# ServoMotor.net
KiCad netlist of a schematic drawn in EAGLE
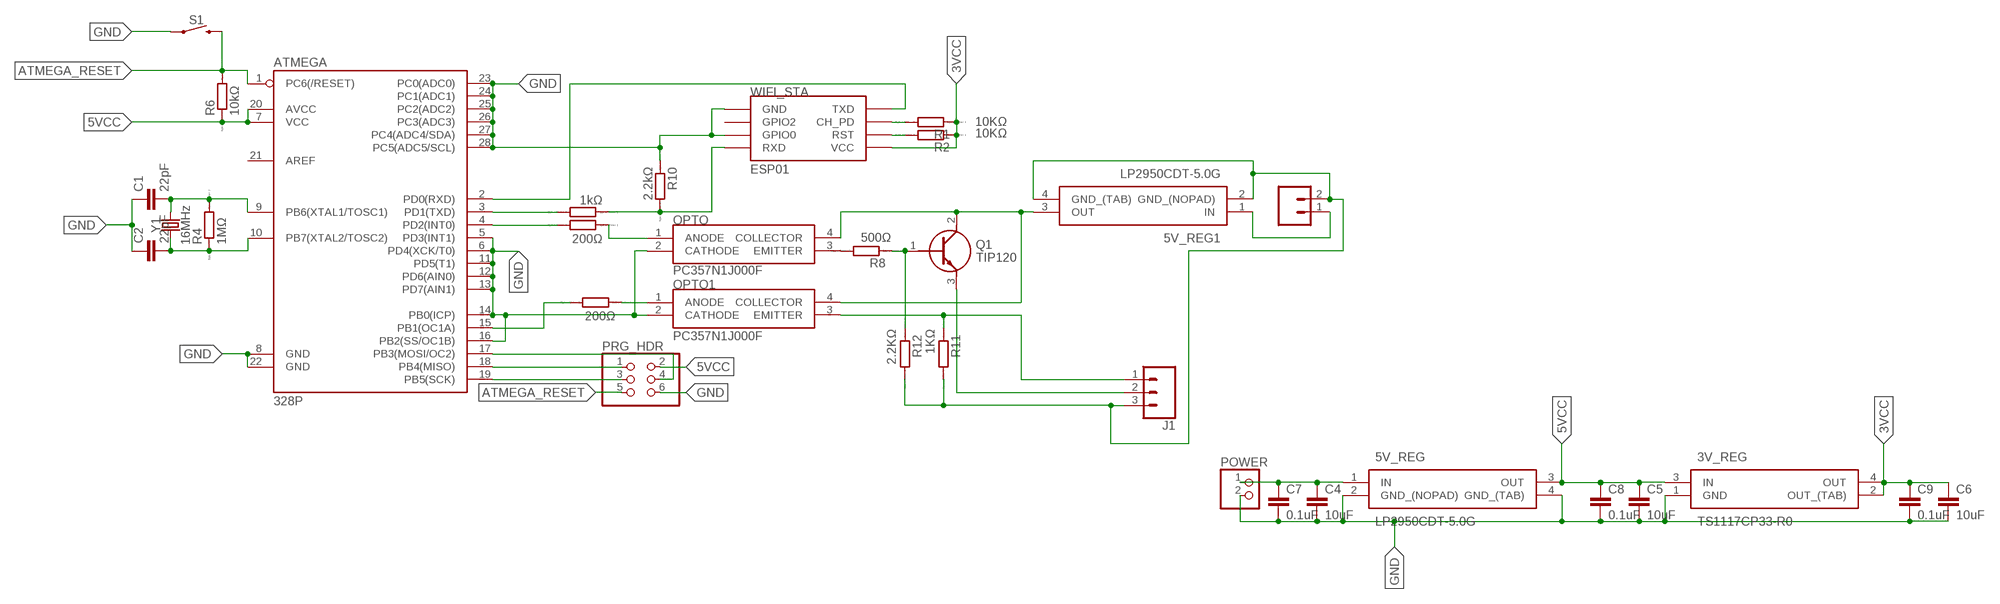
[diagram p0: schematic, sheet 1]

(export (version "E")
  (design (tool "Eeschema 10.0.6"))
  (components
    (comp (ref "3V_REG")
      (value "TS1117CP33-R0")
      (footprint "eagle-import:TO229P990X238-4N")
      (fields
        (field (name "MANUFACTURER_PART_NUMBER") "LP2950CDT-5.0G")
        (field (name "MOUSER_PART_NUMBER") "863-LP2950CDT-5.0G")
        (field (name "RS_PART_NUMBER") "0463593P")
      )
      (libsource (lib "eagle-import") (part "TS1117CP33-R0"))
    )
    (comp (ref "5V_REG")
      (value "LP2950CDT-5.0G")
      (footprint "eagle-import:TO229P990X238-4N")
      (fields
        (field (name "MOUSER_PART_NUMBER") "863-LP2950CDT-5.0G")
        (field (name "RS_PART_NUMBER") "0463593P")
      )
      (libsource (lib "eagle-import") (part "LP2950CDT-5.0G"))
    )
    (comp (ref "5V_REG1")
      (value "LP2950CDT-5.0G")
      (footprint "eagle-import:TO229P990X238-4N")
      (fields
        (field (name "MOUSER_PART_NUMBER") "863-LP2950CDT-5.0G")
        (field (name "RS_PART_NUMBER") "0463593P")
      )
      (libsource (lib "eagle-import") (part "LP2950CDT-5.0G"))
    )
    (comp (ref "ATMEGA")
      (value "328P")
      (footprint "eagle-import:DIP28")
      (libsource (lib "eagle-import") (part "ATMEGA328P_PDIP"))
    )
    (comp (ref "C1")
      (value "22pF")
      (footprint "eagle-import:1206")
      (libsource (lib "eagle-import") (part "1.0UF-1206-50V-10%"))
    )
    (comp (ref "C2")
      (value "22pF")
      (footprint "eagle-import:1206")
      (libsource (lib "eagle-import") (part "1.0UF-1206-50V-10%"))
    )
    (comp (ref "C4")
      (value "10uF")
      (footprint "eagle-import:1206")
      (libsource (lib "eagle-import") (part "1.0UF-1206-50V-10%"))
    )
    (comp (ref "C5")
      (value "10uF")
      (footprint "eagle-import:1206")
      (libsource (lib "eagle-import") (part "1.0UF-1206-50V-10%"))
    )
    (comp (ref "C6")
      (value "10uF")
      (footprint "eagle-import:1206")
      (libsource (lib "eagle-import") (part "1.0UF-1206-50V-10%"))
    )
    (comp (ref "C7")
      (value "0.1uF")
      (footprint "eagle-import:1206")
      (libsource (lib "eagle-import") (part "1.0UF-1206-50V-10%"))
    )
    (comp (ref "C8")
      (value "0.1uF")
      (footprint "eagle-import:1206")
      (libsource (lib "eagle-import") (part "1.0UF-1206-50V-10%"))
    )
    (comp (ref "C9")
      (value "0.1uF")
      (footprint "eagle-import:1206")
      (libsource (lib "eagle-import") (part "1.0UF-1206-50V-10%"))
    )
    (comp (ref "J1")
      (value "CONN_03")
      (footprint "eagle-import:1X03")
      (libsource (lib "eagle-import") (part "CONN_03"))
    )
    (comp (ref "OPTO")
      (value "PC357N1J000F")
      (footprint "eagle-import:SOP254P675X300-4N")
      (fields
        (field (name "MOUSER_PART_NUMBER") "852-PC357N1J000F")
        (field (name "RS_PART_NUMBER") "1460767")
      )
      (libsource (lib "eagle-import") (part "PC357N1J000F"))
    )
    (comp (ref "OPTO1")
      (value "PC357N1J000F")
      (footprint "eagle-import:SOP254P675X300-4N")
      (fields
        (field (name "MOUSER_PART_NUMBER") "852-PC357N1J000F")
        (field (name "RS_PART_NUMBER") "1460767")
      )
      (libsource (lib "eagle-import") (part "PC357N1J000F"))
    )
    (comp (ref "POWER")
      (value "PINHD-1X2")
      (footprint "eagle-import:1X02")
      (libsource (lib "eagle-import") (part "PINHD-1X2"))
    )
    (comp (ref "PRG_HDR")
      (value "PINHD-2X3")
      (footprint "eagle-import:2X03")
      (libsource (lib "eagle-import") (part "PINHD-2X3"))
    )
    (comp (ref "PWR_SERVO")
      (value "CONN_025MM")
      (footprint "eagle-import:SCREWTERMINAL-5MM-2")
      (libsource (lib "eagle-import") (part "CONN_025MM"))
    )
    (comp (ref "Q1")
      (value "TIP120")
      (footprint "eagle-import:TO220")
      (fields (field (name "MOUSER_PART_NUMBER") "512-TIP120"))
      (libsource (lib "eagle-import") (part "TIP120"))
    )
    (comp (ref "R1")
      (value "10KΩ")
      (footprint "eagle-import:R1210")
      (libsource (lib "eagle-import") (part "RR1210"))
    )
    (comp (ref "R2")
      (value "10KΩ")
      (footprint "eagle-import:R1210")
      (libsource (lib "eagle-import") (part "RR1210"))
    )
    (comp (ref "R3")
      (value "200Ω")
      (footprint "eagle-import:R1210")
      (libsource (lib "eagle-import") (part "RR1210"))
    )
    (comp (ref "R4")
      (value "1MΩ")
      (footprint "eagle-import:R1210")
      (libsource (lib "eagle-import") (part "RR1210"))
    )
    (comp (ref "R5")
      (value "200Ω")
      (footprint "eagle-import:R1210")
      (libsource (lib "eagle-import") (part "RR1210"))
    )
    (comp (ref "R6")
      (value "10kΩ")
      (footprint "eagle-import:R1210")
      (libsource (lib "eagle-import") (part "RR1210"))
    )
    (comp (ref "R8")
      (value "500Ω")
      (footprint "eagle-import:R1210")
      (libsource (lib "eagle-import") (part "RR1210"))
    )
    (comp (ref "R9")
      (value "1kΩ")
      (footprint "eagle-import:R1210")
      (libsource (lib "eagle-import") (part "RR1210"))
    )
    (comp (ref "R10")
      (value "2.2kΩ")
      (footprint "eagle-import:R1210")
      (libsource (lib "eagle-import") (part "RR1210"))
    )
    (comp (ref "R11")
      (value "1KΩ")
      (footprint "eagle-import:R1210")
      (libsource (lib "eagle-import") (part "RR1210"))
    )
    (comp (ref "R12")
      (value "2.2KΩ")
      (footprint "eagle-import:R1210")
      (libsource (lib "eagle-import") (part "RR1210"))
    )
    (comp (ref "S1")
      (value "MOMENTARY-SWITCH-SPST-PTH-6.0MM")
      (footprint "eagle-import:TACTILE_SWITCH_PTH_6.0MM")
      (libsource (lib "eagle-import") (part "MOMENTARY-SWITCH-SPST-PTH-6.0MM"))
    )
    (comp (ref "WIFI_STA")
      (value "ESP01")
      (footprint "eagle-import:ESP01")
      (libsource (lib "eagle-import") (part "ESP01"))
    )
    (comp (ref "Y1")
      (value "16MHz")
      (footprint "eagle-import:HC49UP")
      (libsource (lib "eagle-import") (part "CRYSTAL-8MHZSMD-HC49UP"))
    )
  )
  (nets
    (net (code "1") (name "3VCC") (class "Default")
      (node (ref "3V_REG") (pin "2") (pinfunction "OUT_(TAB)_2") (pintype "output"))
      (node (ref "3V_REG") (pin "4") (pinfunction "OUT_4") (pintype "output"))
      (node (ref "C6") (pin "1") (pinfunction "1_1") (pintype "passive"))
      (node (ref "C9") (pin "1") (pinfunction "1_1") (pintype "passive"))
      (node (ref "R1") (pin "1") (pinfunction "1_1") (pintype "passive"))
      (node (ref "R2") (pin "1") (pinfunction "1_1") (pintype "passive"))
      (node (ref "WIFI_STA") (pin "VCC") (pinfunction "VCC_VCC") (pintype "bidirectional"))
    )
    (net (code "2") (name "5VCC") (class "Default")
      (node (ref "3V_REG") (pin "3") (pinfunction "IN_3") (pintype "input"))
      (node (ref "5V_REG") (pin "3") (pinfunction "OUT_3") (pintype "output"))
      (node (ref "ATMEGA") (pin "20") (pinfunction "AVCC_20") (pintype "bidirectional"))
      (node (ref "ATMEGA") (pin "7") (pinfunction "VCC_7") (pintype "bidirectional"))
      (node (ref "C5") (pin "1") (pinfunction "1_1") (pintype "passive"))
      (node (ref "C8") (pin "1") (pinfunction "1_1") (pintype "passive"))
      (node (ref "PRG_HDR") (pin "2") (pinfunction "2_2") (pintype "passive"))
      (node (ref "R6") (pin "1") (pinfunction "1_1") (pintype "passive"))
    )
    (net (code "3") (name "ATMEGA_RESET") (class "Default")
      (node (ref "ATMEGA") (pin "1") (pinfunction "PC6(/RESET)_1") (pintype "bidirectional"))
      (node (ref "PRG_HDR") (pin "5") (pinfunction "5_5") (pintype "passive"))
      (node (ref "R6") (pin "2") (pinfunction "2_2") (pintype "passive"))
      (node (ref "S1") (pin "3") (pinfunction "2_3") (pintype "passive"))
    )
    (net (code "4") (name "GND") (class "Default")
      (node (ref "3V_REG") (pin "1") (pinfunction "GND_1") (pintype "power_in"))
      (node (ref "5V_REG") (pin "2") (pinfunction "GND_(NOPAD)_2") (pintype "power_in"))
      (node (ref "5V_REG") (pin "4") (pinfunction "GND_(TAB)_4") (pintype "power_in"))
      (node (ref "ATMEGA") (pin "11") (pinfunction "PD5(T1)_11") (pintype "bidirectional"))
      (node (ref "ATMEGA") (pin "12") (pinfunction "PD6(AIN0)_12") (pintype "bidirectional"))
      (node (ref "ATMEGA") (pin "13") (pinfunction "PD7(AIN1)_13") (pintype "bidirectional"))
      (node (ref "ATMEGA") (pin "14") (pinfunction "PB0(ICP)_14") (pintype "bidirectional"))
      (node (ref "ATMEGA") (pin "16") (pinfunction "PB2(SS/OC1B)_16") (pintype "bidirectional"))
      (node (ref "ATMEGA") (pin "22") (pinfunction "GND_22") (pintype "bidirectional"))
      (node (ref "ATMEGA") (pin "23") (pinfunction "PC0(ADC0)_23") (pintype "bidirectional"))
      (node (ref "ATMEGA") (pin "24") (pinfunction "PC1(ADC1)_24") (pintype "bidirectional"))
      (node (ref "ATMEGA") (pin "25") (pinfunction "PC2(ADC2)_25") (pintype "bidirectional"))
      (node (ref "ATMEGA") (pin "26") (pinfunction "PC3(ADC3)_26") (pintype "bidirectional"))
      (node (ref "ATMEGA") (pin "27") (pinfunction "PC4(ADC4/SDA)_27") (pintype "bidirectional"))
      (node (ref "ATMEGA") (pin "28") (pinfunction "PC5(ADC5/SCL)_28") (pintype "bidirectional"))
      (node (ref "ATMEGA") (pin "5") (pinfunction "PD3(INT1)_5") (pintype "bidirectional"))
      (node (ref "ATMEGA") (pin "6") (pinfunction "PD4(XCK/T0)_6") (pintype "bidirectional"))
      (node (ref "ATMEGA") (pin "8") (pinfunction "GND_8") (pintype "bidirectional"))
      (node (ref "C1") (pin "1") (pinfunction "1_1") (pintype "passive"))
      (node (ref "C2") (pin "1") (pinfunction "1_1") (pintype "passive"))
      (node (ref "C4") (pin "2") (pinfunction "2_2") (pintype "passive"))
      (node (ref "C5") (pin "2") (pinfunction "2_2") (pintype "passive"))
      (node (ref "C6") (pin "2") (pinfunction "2_2") (pintype "passive"))
      (node (ref "C7") (pin "2") (pinfunction "2_2") (pintype "passive"))
      (node (ref "C8") (pin "2") (pinfunction "2_2") (pintype "passive"))
      (node (ref "C9") (pin "2") (pinfunction "2_2") (pintype "passive"))
      (node (ref "OPTO") (pin "2") (pinfunction "CATHODE_2") (pintype "bidirectional"))
      (node (ref "OPTO1") (pin "2") (pinfunction "CATHODE_2") (pintype "bidirectional"))
      (node (ref "POWER") (pin "2") (pinfunction "2_2") (pintype "passive"))
      (node (ref "PRG_HDR") (pin "6") (pinfunction "6_6") (pintype "passive"))
      (node (ref "R10") (pin "1") (pinfunction "1_1") (pintype "passive"))
      (node (ref "S1") (pin "1") (pinfunction "1_1") (pintype "passive"))
      (node (ref "WIFI_STA") (pin "GND") (pinfunction "GND_GND") (pintype "bidirectional"))
      (node (ref "WIFI_STA") (pin "GPIO0") (pinfunction "GPIO0_GPIO0") (pintype "bidirectional"))
    )
    (net (code "5") (name "Net-(5V_REG-IN)") (class "Default")
      (node (ref "5V_REG") (pin "1") (pinfunction "IN_1") (pintype "input"))
      (node (ref "C4") (pin "1") (pinfunction "1_1") (pintype "passive"))
      (node (ref "C7") (pin "1") (pinfunction "1_1") (pintype "passive"))
      (node (ref "POWER") (pin "1") (pinfunction "1_1") (pintype "passive"))
    )
    (net (code "6") (name "Net-(5V_REG1-GND_(NOPAD))") (class "Default")
      (node (ref "5V_REG1") (pin "2") (pinfunction "GND_(NOPAD)_2") (pintype "power_in"))
      (node (ref "5V_REG1") (pin "4") (pinfunction "GND_(TAB)_4") (pintype "power_in"))
      (node (ref "J1") (pin "3") (pinfunction "3_3") (pintype "passive"))
      (node (ref "PWR_SERVO") (pin "2") (pinfunction "2_2") (pintype "passive"))
      (node (ref "R11") (pin "2") (pinfunction "2_2") (pintype "passive"))
      (node (ref "R12") (pin "2") (pinfunction "2_2") (pintype "passive"))
    )
    (net (code "7") (name "Net-(5V_REG1-IN)") (class "Default")
      (node (ref "5V_REG1") (pin "1") (pinfunction "IN_1") (pintype "input"))
      (node (ref "PWR_SERVO") (pin "1") (pinfunction "1_1") (pintype "passive"))
    )
    (net (code "8") (name "Net-(5V_REG1-OUT)") (class "Default")
      (node (ref "5V_REG1") (pin "3") (pinfunction "OUT_3") (pintype "output"))
      (node (ref "OPTO") (pin "4") (pinfunction "COLLECTOR_4") (pintype "bidirectional"))
      (node (ref "OPTO1") (pin "4") (pinfunction "COLLECTOR_4") (pintype "bidirectional"))
      (node (ref "Q1") (pin "2") (pinfunction "C_2") (pintype "bidirectional"))
    )
    (net (code "9") (name "Net-(ATMEGA-PB1(OC1A))") (class "Default")
      (node (ref "ATMEGA") (pin "15") (pinfunction "PB1(OC1A)_15") (pintype "bidirectional"))
      (node (ref "R5") (pin "2") (pinfunction "2_2") (pintype "passive"))
    )
    (net (code "10") (name "Net-(ATMEGA-PB3(MOSI{slash}OC2))") (class "Default")
      (node (ref "ATMEGA") (pin "17") (pinfunction "PB3(MOSI/OC2)_17") (pintype "bidirectional"))
      (node (ref "PRG_HDR") (pin "4") (pinfunction "4_4") (pintype "passive"))
    )
    (net (code "11") (name "Net-(ATMEGA-PB4(MISO))") (class "Default")
      (node (ref "ATMEGA") (pin "18") (pinfunction "PB4(MISO)_18") (pintype "bidirectional"))
      (node (ref "PRG_HDR") (pin "1") (pinfunction "1_1") (pintype "passive"))
    )
    (net (code "12") (name "Net-(ATMEGA-PB5(SCK))") (class "Default")
      (node (ref "ATMEGA") (pin "19") (pinfunction "PB5(SCK)_19") (pintype "bidirectional"))
      (node (ref "PRG_HDR") (pin "3") (pinfunction "3_3") (pintype "passive"))
    )
    (net (code "13") (name "Net-(ATMEGA-PB6(XTAL1{slash}TOSC1))") (class "Default")
      (node (ref "ATMEGA") (pin "9") (pinfunction "PB6(XTAL1/TOSC1)_9") (pintype "bidirectional"))
      (node (ref "C1") (pin "2") (pinfunction "2_2") (pintype "passive"))
      (node (ref "R4") (pin "2") (pinfunction "2_2") (pintype "passive"))
      (node (ref "Y1") (pin "2") (pinfunction "2_2") (pintype "passive"))
    )
    (net (code "14") (name "Net-(ATMEGA-PB7(XTAL2{slash}TOSC2))") (class "Default")
      (node (ref "ATMEGA") (pin "10") (pinfunction "PB7(XTAL2/TOSC2)_10") (pintype "bidirectional"))
      (node (ref "C2") (pin "2") (pinfunction "2_2") (pintype "passive"))
      (node (ref "R4") (pin "1") (pinfunction "1_1") (pintype "passive"))
      (node (ref "Y1") (pin "1") (pinfunction "1_1") (pintype "passive"))
    )
    (net (code "15") (name "Net-(ATMEGA-PD0(RXD))") (class "Default")
      (node (ref "ATMEGA") (pin "2") (pinfunction "PD0(RXD)_2") (pintype "bidirectional"))
      (node (ref "WIFI_STA") (pin "TX") (pinfunction "TXD_TX") (pintype "bidirectional"))
    )
    (net (code "16") (name "Net-(ATMEGA-PD1(TXD))") (class "Default")
      (node (ref "ATMEGA") (pin "3") (pinfunction "PD1(TXD)_3") (pintype "bidirectional"))
      (node (ref "R9") (pin "2") (pinfunction "2_2") (pintype "passive"))
    )
    (net (code "17") (name "Net-(ATMEGA-PD2(INT0))") (class "Default")
      (node (ref "ATMEGA") (pin "4") (pinfunction "PD2(INT0)_4") (pintype "bidirectional"))
      (node (ref "R3") (pin "2") (pinfunction "2_2") (pintype "passive"))
    )
    (net (code "18") (name "Net-(OPTO-ANODE)") (class "Default")
      (node (ref "OPTO") (pin "1") (pinfunction "ANODE_1") (pintype "bidirectional"))
      (node (ref "R3") (pin "1") (pinfunction "1_1") (pintype "passive"))
    )
    (net (code "19") (name "Net-(OPTO-EMITTER)") (class "Default")
      (node (ref "OPTO") (pin "3") (pinfunction "EMITTER_3") (pintype "bidirectional"))
      (node (ref "R8") (pin "2") (pinfunction "2_2") (pintype "passive"))
    )
    (net (code "20") (name "Net-(OPTO1-ANODE)") (class "Default")
      (node (ref "OPTO1") (pin "1") (pinfunction "ANODE_1") (pintype "bidirectional"))
      (node (ref "R5") (pin "1") (pinfunction "1_1") (pintype "passive"))
    )
    (net (code "21") (name "Net-(OPTO1-EMITTER)") (class "Default")
      (node (ref "J1") (pin "1") (pinfunction "1_1") (pintype "passive"))
      (node (ref "OPTO1") (pin "3") (pinfunction "EMITTER_3") (pintype "bidirectional"))
      (node (ref "R11") (pin "1") (pinfunction "1_1") (pintype "passive"))
    )
    (net (code "22") (name "Net-(Q1-B)") (class "Default")
      (node (ref "Q1") (pin "1") (pinfunction "B_1") (pintype "bidirectional"))
      (node (ref "R12") (pin "1") (pinfunction "1_1") (pintype "passive"))
      (node (ref "R8") (pin "1") (pinfunction "1_1") (pintype "passive"))
    )
    (net (code "23") (name "Net-(Q1-E)") (class "Default")
      (node (ref "J1") (pin "2") (pinfunction "2_2") (pintype "passive"))
      (node (ref "Q1") (pin "3") (pinfunction "E_3") (pintype "bidirectional"))
    )
    (net (code "24") (name "Net-(R1-Pad2)") (class "Default")
      (node (ref "R1") (pin "2") (pinfunction "2_2") (pintype "passive"))
      (node (ref "WIFI_STA") (pin "CH_PD") (pinfunction "CH_PD_CH_PD") (pintype "bidirectional"))
    )
    (net (code "25") (name "Net-(R2-Pad2)") (class "Default")
      (node (ref "R2") (pin "2") (pinfunction "2_2") (pintype "passive"))
      (node (ref "WIFI_STA") (pin "RST") (pinfunction "RST_RST") (pintype "bidirectional"))
    )
    (net (code "26") (name "Net-(WIFI_STA-RXD)") (class "Default")
      (node (ref "R10") (pin "2") (pinfunction "2_2") (pintype "passive"))
      (node (ref "R9") (pin "1") (pinfunction "1_1") (pintype "passive"))
      (node (ref "WIFI_STA") (pin "RX") (pinfunction "RXD_RX") (pintype "bidirectional"))
    )
    (net (code "27") (name "unconnected-(ATMEGA-AREF-Pad21)") (class "Default")
      (node (ref "ATMEGA") (pin "21") (pinfunction "AREF_21") (pintype "bidirectional"))
    )
    (net (code "28") (name "unconnected-(WIFI_STA-PadGPIO2)") (class "Default")
      (node (ref "WIFI_STA") (pin "GPIO2") (pinfunction "GPIO2_GPIO2") (pintype "bidirectional"))
    )
  )
)
